# Voltage_generation.net
KiCad netlist of a schematic drawn in Altium Designer
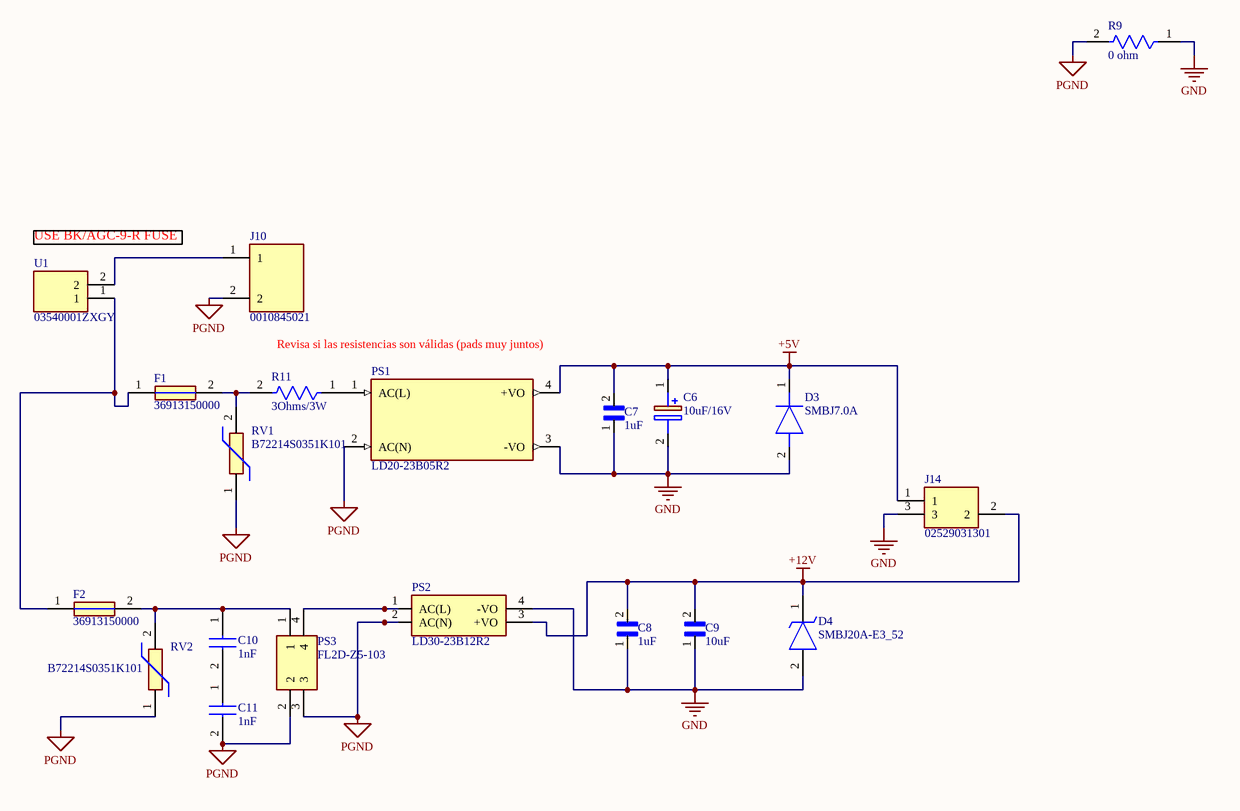
[diagram p0: Voltage_generation.SchDoc]

(export (version "E")
  (design (tool "Eeschema 10.0.6"))
  (components
    (comp (ref "C6")
      (value "10uF/16V")
      (footprint "PcbLib1:CAPPRD200W52D500H1250")
      (description "Capacitor Polarised")
      (fields
        (field (name "MANUFACTURER_PART_NUMBER") "860010372001")
        (field (name "MOUSER PART NUMBER") "710-860010372001")
      )
      (libsource (lib "*") (part "860010372001"))
    )
    (comp (ref "C7")
      (value "1uF")
      (footprint "1206C")
      (description "1 µF ±10% 50V Capacitores cerámicos X7R 1206 (3216 métrico)")
      (fields
        (field (name "MANUFACTURER") "Samsung")
        (field (name "MANUFACTURER PART NUMBER") "CL31B105KBHNNNE")
      )
      (libsource (lib "Schlib1") (part "Ceramic_Capacitor"))
    )
    (comp (ref "C8")
      (value "1uF")
      (footprint "1206C")
      (description "1 µF ±10% 50V Capacitores cerámicos X7R 1206 (3216 métrico)")
      (fields
        (field (name "MANUFACTURER") "Samsung")
        (field (name "MANUFACTURER PART NUMBER") "CL31B105KCHSNNE")
      )
      (libsource (lib "Schlib1") (part "Ceramic_Capacitor"))
    )
    (comp (ref "C9")
      (value "10uF")
      (footprint "1206C")
      (description "1 µF ±10% 50V Capacitores cerámicos X7R 1206 (3216 métrico)")
      (fields
        (field (name "MANUFACTURER") "Samsung")
        (field (name "MANUFACTURER PART NUMBER") "CL31A106MBHNNNE")
      )
      (libsource (lib "Schlib1") (part "Ceramic_Capacitor"))
    )
    (comp (ref "C10")
      (value "1nF")
      (footprint "PcbLib1:C907U102MYVDBA7317")
      (description "Capacitor")
      (fields
        (field (name "MANUFACTURER_PART_NUMBER") "C907U102MYVDBA7317")
        (field (name "MOUSER PART NUMBER") "80-C907U102MYVDBAP")
      )
      (libsource (lib "*") (part "C907U102MYVDBA7317"))
    )
    (comp (ref "C11")
      (value "1nF")
      (footprint "PcbLib1:C907U102MYVDBA7317")
      (description "Capacitor")
      (fields
        (field (name "MANUFACTURER_PART_NUMBER") "C907U102MYVDBA7317")
        (field (name "MOUSER PART NUMBER") "80-C907U102MYVDBAP")
      )
      (libsource (lib "*") (part "C907U102MYVDBA7317"))
    )
    (comp (ref "D3")
      (value "SMBJ7.0A")
      (footprint "PcbLib1:DIOM5336X244N")
      (description "Diode")
      (libsource (lib "*") (part "SMBJ7.0A"))
    )
    (comp (ref "D4")
      (value "SMBJ20A-E3_52")
      (footprint "PcbLib1:DIOM5436X244N")
      (description "TVS Diode (Uni-directional)")
      (fields
        (field (name "MANUFACTURER_PART_NUMBER") "SMBJ20A-E3/52")
        (field (name "MOUSER PART NUMBER") "625-SMBJ20A-E3")
      )
      (libsource (lib "*") (part "SMBJ20A-E3_52"))
    )
    (comp (ref "F1")
      (value "36913150000")
      (footprint "PcbLib1:36913150000")
      (description "Fuse")
      (fields (field (name "MOUSER PART NUMBER") "576-36913150000"))
      (libsource (lib "*") (part "36913150000"))
    )
    (comp (ref "F2")
      (value "36913150000")
      (footprint "PcbLib1:36913150000")
      (description "Fuse")
      (fields (field (name "MOUSER PART NUMBER") "576-36913150000"))
      (libsource (lib "*") (part "36913150000"))
    )
    (comp (ref "J10")
      (value "0010845021")
      (footprint "0010845021_MOLEX")
      (description "Connector")
      (fields (field (name "MANUFACTURER") "MOLEX"))
      (libsource (lib "Schlib1") (part "0010845021"))
    )
    (comp (ref "J14")
      (value "02529031301")
      (footprint "PcbLib1:02529031301")
      (description "Connector")
      (fields (field (name "MOUSER PART NUMBER") "617-02529031301"))
      (libsource (lib "*") (part "02529031301"))
    )
    (comp (ref "PS1")
      (value "LD20-23B05R2")
      (footprint "CONV_LD20-23B05R2")
      (description "Enclosed AC DC Converters 1 Uitgang 5V - - - 4A 85 ~ 305 VAC, 100 ~ 430 VDC Input")
      (fields
        (field (name "DIGI-KEY_PART_NUMBER") "2725-LD20-23B05R2-ND")
        (field (name "MANUFACTURER") "Mornsun America, LLC")
      )
      (libsource (lib "Schlib1") (part "LD20-23B05R2"))
    )
    (comp (ref "PS2")
      (value "LD30-23B12R2")
      (footprint "PcbLib1:LD3023B12R2")
      (description "Power Supply")
      (libsource (lib "*") (part "LD30-23B12R2"))
    )
    (comp (ref "PS3")
      (value "FL2D-Z5-103")
      (footprint "PcbLib1:FL2DZ5103")
      (description "Power Supply")
      (libsource (lib "*") (part "FL2D-Z5-103"))
    )
    (comp (ref "R9")
      (value "0 ohm")
      (footprint "0603R")
      (fields
        (field (name "MANUFACTURER") "Yageo")
        (field (name "MANUFACTURER PART NUMBER") "RC0603FR-070RL")
      )
      (libsource (lib "Schlib1") (part "Resistor"))
    )
    (comp (ref "R11")
      (value "3Ohms/3W")
      (footprint "Rohm_LTR100_IPC_A")
      (fields (field (name "MANUFACTURER") "Rohm") (field (name "MANUFACTURER PART NUMBER") "LTR100JZPJ3R0"))
      (libsource (lib "Schlib1") (part "Resistor"))
    )
    (comp (ref "RV1")
      (value "B72214S0351K101")
      (footprint "PcbLib1:B72214S0351K101")
      (description "Varistor")
      (libsource (lib "*") (part "B72214S0351K101"))
    )
    (comp (ref "RV2")
      (value "B72214S0351K101")
      (footprint "PcbLib1:B72214S0351K101")
      (description "Varistor")
      (libsource (lib "*") (part "B72214S0351K101"))
    )
    (comp (ref "U1")
      (value "03540001ZXGY")
      (footprint "PcbLib1:Fuse_1")
      (description "Undefined or Miscellaneous")
      (fields (field (name "MOUSER PART NUMBER") "576-03540001ZXGY"))
      (libsource (lib "Schlib1") (part "03540001ZXGY"))
    )
  )
  (nets
    (net (code "1") (name "+5V") (class "Default")
      (node (ref "C6") (pin "1") (pinfunction "+_1") (pintype "passive"))
      (node (ref "C7") (pin "2") (pinfunction "2_2") (pintype "passive"))
      (node (ref "D3") (pin "1") (pinfunction "K_1") (pintype "passive"))
      (node (ref "J14") (pin "1") (pinfunction "1_1") (pintype "passive"))
      (node (ref "PS1") (pin "4") (pinfunction "+VO_4") (pintype "output"))
    )
    (net (code "2") (name "+12V") (class "Default")
      (node (ref "C8") (pin "2") (pinfunction "2_2") (pintype "passive"))
      (node (ref "C9") (pin "2") (pinfunction "2_2") (pintype "passive"))
      (node (ref "D4") (pin "1") (pinfunction "K_1") (pintype "passive"))
      (node (ref "J14") (pin "2") (pinfunction "2_2") (pintype "passive"))
      (node (ref "PS2") (pin "3") (pinfunction "+VO_3") (pintype "passive"))
    )
    (net (code "3") (name "GND") (class "Default")
      (node (ref "C6") (pin "2") (pinfunction "-_2") (pintype "passive"))
      (node (ref "C7") (pin "1") (pinfunction "1_1") (pintype "passive"))
      (node (ref "C8") (pin "1") (pinfunction "1_1") (pintype "passive"))
      (node (ref "C9") (pin "1") (pinfunction "1_1") (pintype "passive"))
      (node (ref "D3") (pin "2") (pinfunction "A_2") (pintype "passive"))
      (node (ref "D4") (pin "2") (pinfunction "A_2") (pintype "passive"))
      (node (ref "J14") (pin "3") (pinfunction "3_3") (pintype "passive"))
      (node (ref "PS1") (pin "3") (pinfunction "-VO_3") (pintype "output"))
      (node (ref "PS2") (pin "4") (pinfunction "-VO_4") (pintype "passive"))
      (node (ref "R9") (pin "1") (pinfunction "1_1") (pintype "passive"))
    )
    (net (code "4") (name "Net-(C10-Pad1)") (class "Default")
      (node (ref "C10") (pin "1") (pinfunction "1_1") (pintype "passive"))
      (node (ref "F2") (pin "2") (pinfunction "2_2") (pintype "passive"))
      (node (ref "PS3") (pin "1") (pinfunction "1_1") (pintype "passive"))
      (node (ref "RV2") (pin "2") (pinfunction "2_2") (pintype "passive"))
    )
    (net (code "5") (name "Net-(C10-Pad2)") (class "Default")
      (node (ref "C10") (pin "2") (pinfunction "2_2") (pintype "passive"))
      (node (ref "C11") (pin "1") (pinfunction "1_1") (pintype "passive"))
    )
    (net (code "6") (name "Net-(F1-Pad1)") (class "Default")
      (node (ref "F1") (pin "1") (pinfunction "1_1") (pintype "passive"))
      (node (ref "F2") (pin "1") (pinfunction "1_1") (pintype "passive"))
      (node (ref "U1") (pin "1") (pinfunction "1_1") (pintype "passive"))
    )
    (net (code "7") (name "Net-(F1-Pad2)") (class "Default")
      (node (ref "F1") (pin "2") (pinfunction "2_2") (pintype "passive"))
      (node (ref "R11") (pin "2") (pinfunction "2_2") (pintype "passive"))
      (node (ref "RV1") (pin "2") (pinfunction "2_2") (pintype "passive"))
    )
    (net (code "8") (name "Net-(J10-Pad1)") (class "Default")
      (node (ref "J10") (pin "1") (pinfunction "1_1") (pintype "passive"))
      (node (ref "U1") (pin "2") (pinfunction "2_2") (pintype "passive"))
    )
    (net (code "9") (name "Net-(PS1-AC(L))") (class "Default")
      (node (ref "PS1") (pin "1") (pinfunction "AC(L)_1") (pintype "input"))
      (node (ref "R11") (pin "1") (pinfunction "1_1") (pintype "passive"))
    )
    (net (code "10") (name "Net-(PS2-AC(L))") (class "Default")
      (node (ref "PS2") (pin "1") (pinfunction "AC(L)_1") (pintype "passive"))
      (node (ref "PS3") (pin "4") (pinfunction "4_4") (pintype "passive"))
    )
    (net (code "11") (name "PGND") (class "Default")
      (node (ref "C11") (pin "2") (pinfunction "2_2") (pintype "passive"))
      (node (ref "J10") (pin "2") (pinfunction "2_2") (pintype "passive"))
      (node (ref "PS1") (pin "2") (pinfunction "AC(N)_2") (pintype "input"))
      (node (ref "PS2") (pin "2") (pinfunction "AC(N)_2") (pintype "passive"))
      (node (ref "PS3") (pin "2") (pinfunction "2_2") (pintype "passive"))
      (node (ref "PS3") (pin "3") (pinfunction "3_3") (pintype "passive"))
      (node (ref "R9") (pin "2") (pinfunction "2_2") (pintype "passive"))
      (node (ref "RV1") (pin "1") (pinfunction "1_1") (pintype "passive"))
      (node (ref "RV2") (pin "1") (pinfunction "1_1") (pintype "passive"))
    )
  )
)
